# 12v-5v_conventer.net
KiCad netlist of a schematic drawn in Altium Designer
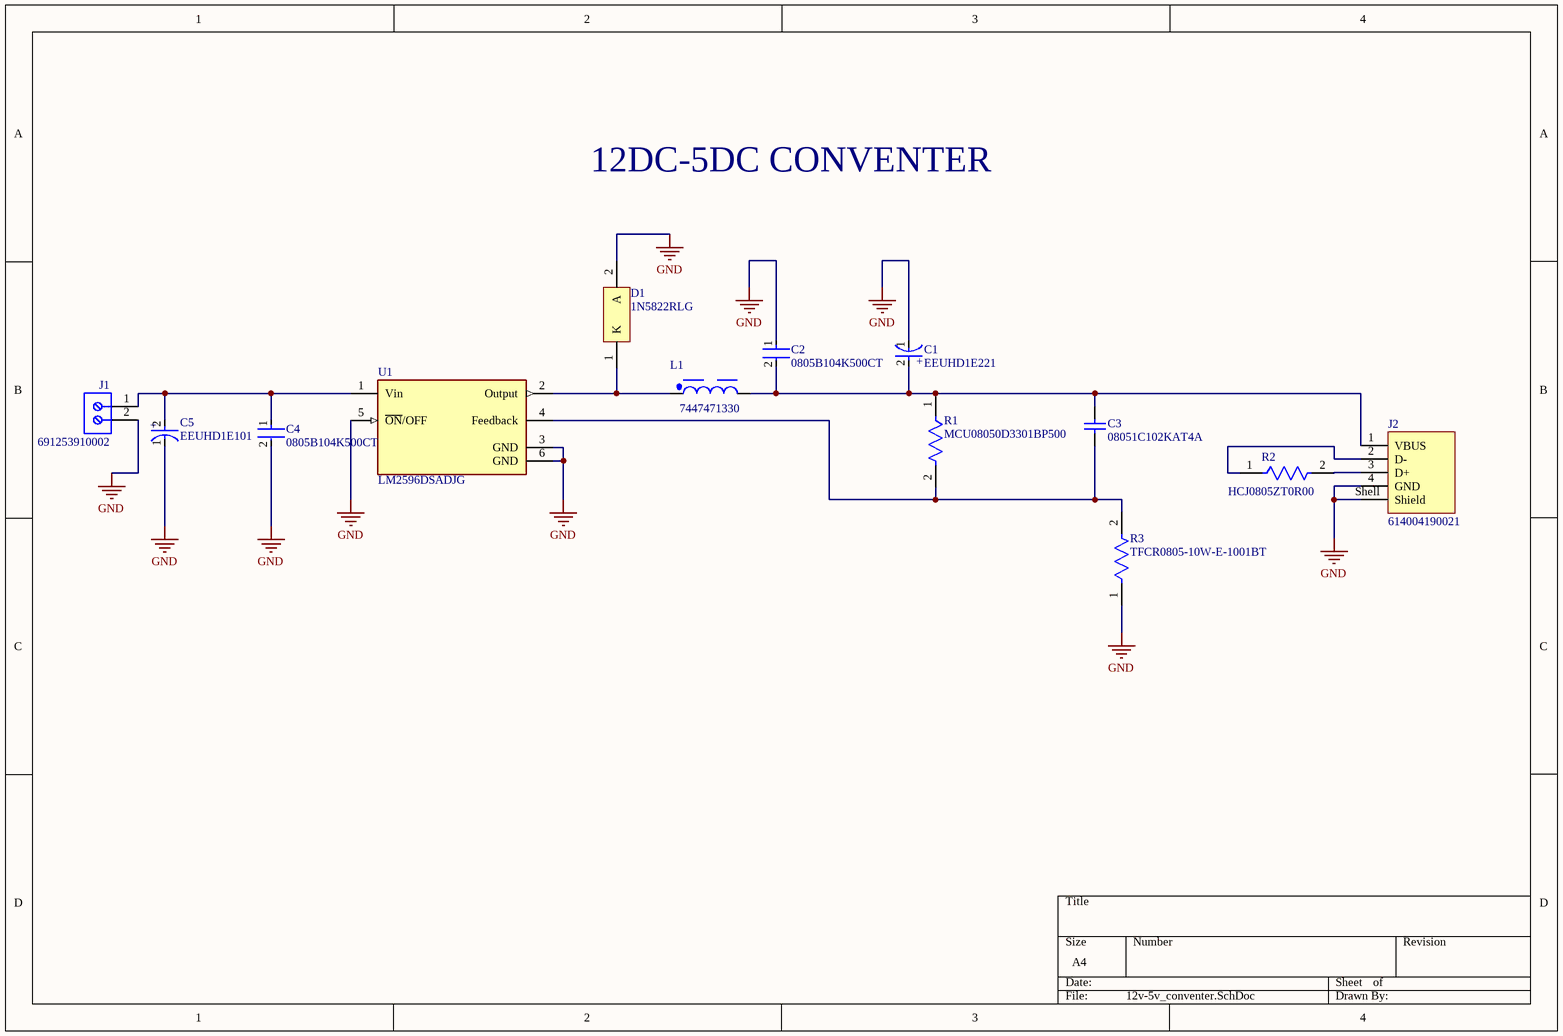
[diagram p0: 12v-5v_conventer.SchDoc]

(export (version "E")
  (design (tool "Eeschema 10.0.6"))
  (components
    (comp (ref "C1")
      (value "EEUHD1E221")
      (footprint "FP-RAD-TH-D_8_0_5-L_11_5-MFG")
      (description "Aluminum Electrolytic Capacitors (Radial Lead Type) AEC-Q200 Qualified 220uF ±20% 25V")
      (fields (field (name "VOLTAGE") "25V") (field (name "TOLERANCE") "20%"))
      (libsource (lib "Altium Content Vault") (part "a00bbbee19879c290e62620ae7e47b1"))
    )
    (comp (ref "C2")
      (value "0805B104K500CT")
      (footprint "FP-0805B-IPC_C")
      (description "CAP CER 0.1UF 50V X7R 0805")
      (fields (field (name "VOLTAGE") "50V") (field (name "TOLERANCE") "10%"))
      (libsource (lib "Altium Content Vault") (part "02cd4be3c70576c341d710602a673aa"))
    )
    (comp (ref "C3")
      (value "08051C102KAT4A")
      (footprint "CAPC2013X94X50LL20T25")
      (fields (field (name "MANUFACTURER") "AVX Interconnect / Elco"))
      (libsource (lib "Altium Content Vault") (part "CAP"))
    )
    (comp (ref "C4")
      (value "0805B104K500CT")
      (footprint "FP-0805B-IPC_C")
      (description "CAP CER 0.1UF 50V X7R 0805")
      (fields (field (name "VOLTAGE") "50V") (field (name "TOLERANCE") "10%"))
      (libsource (lib "Altium Content Vault") (part "02cd4be3c70576c341d710602a673aa"))
    )
    (comp (ref "C5")
      (value "EEUHD1E101")
      (footprint "FP-RAD-TH-D_6_3_0_5-L_11-MFG")
      (description "Aluminum Electrolytic Capacitors (Radial Lead Type) AEC-Q200 Qualified 100uF ±20% 25V")
      (fields (field (name "TOLERANCE") "20%") (field (name "VOLTAGE") "25V"))
      (libsource (lib "Altium Content Vault") (part "a00bbbee19879c290e62620ae7e47b1"))
    )
    (comp (ref "D1")
      (value "1N5822RLG")
      (footprint "ONSC-AXIAL_LEAD-2-267-05_V")
      (description "Rectifier, 2-Pin Axial_Lead, Pb-Free, Tape and Reel")
      (fields (field (name "MANUFACTURER") "On Semiconductor"))
      (libsource (lib "Altium Content Vault") (part "ONSC-D-K1A2-2_A"))
    )
    (comp (ref "J1")
      (value "691253910002")
      (footprint "691253910002")
      (description "Terminal Block, 7.5MM Pitch, Horizontal, Rising Cage Clamp, 12-30 AWG, 2 Pin")
      (libsource (lib "Altium Content Vault") (part "TBL - 1R - 02P - Screw"))
    )
    (comp (ref "J2")
      (value "614004190021")
      (footprint "614004190021")
      (libsource (lib "Altium Content Vault") (part "USB 2.0_Type A_Receptacle_1 Port"))
    )
    (comp (ref "L1")
      (value "7447471330")
      (footprint "WE-TIS_1111")
      (description "Inductor Power Shielded Wirewound 33uH 20% 1KHz Ferrite 3.6A 61mOhm DCR RDL Tray")
      (fields (field (name "TOLERANCE") "20%"))
      (libsource (lib "Altium Content Vault") (part "Inductor - 2"))
    )
    (comp (ref "R1")
      (value "MCU08050D3301BP500")
      (footprint "FP-MCU0805-IPC_A")
      (description "RES 1.05K OHM 0.5% 1/5W 0805")
      (fields (field (name "TOLERANCE") "0.1%"))
      (libsource (lib "Altium Content Vault") (part "1029c3af85768c4190bb7ad29bc67b5"))
    )
    (comp (ref "R2")
      (value "HCJ0805ZT0R00")
      (footprint "FP-HCJ0805-MFG")
      (description "RES 0 OHM JUMPER 1/2W 0805")
      (libsource (lib "Altium Content Vault") (part "1029c3af85768c4190bb7ad29bc67b5"))
    )
    (comp (ref "R3")
      (value "TFCR0805-10W-E-1001BT")
      (footprint "FP-TFCR0805-IPC_A")
      (description "RES Thin Film,  1kΩ, 0.1%, 0.1W, 25ppm/°C, 0805")
      (libsource (lib "Altium Content Vault") (part "1029c3af85768c4190bb7ad29bc67b5"))
    )
    (comp (ref "U1")
      (value "LM2596DSADJG")
      (footprint "FP-936A-02-MFG")
      (description "IC REG MULT CONFG ADJ 3A D2PAK-5")
      (fields
        (field (name "OCTOPART") "https://octopart.com/lm2596dsadjg-on+semiconductor-12437034")
        (field (name "MANUFACTURER") "ON Semiconductor")
      )
      (libsource (lib "Altium Content Vault") (part "6e009c68f80b765d55aa2e30e527964"))
    )
  )
  (nets
    (net (code "1") (name "GND") (class "Default")
      (node (ref "C1") (pin "1") (pinfunction "C_1") (pintype "passive"))
      (node (ref "C2") (pin "1") (pinfunction "1_1") (pintype "passive"))
      (node (ref "C4") (pin "2") (pinfunction "2_2") (pintype "passive"))
      (node (ref "C5") (pin "1") (pinfunction "C_1") (pintype "passive"))
      (node (ref "D1") (pin "2") (pinfunction "A_2") (pintype "passive"))
      (node (ref "J1") (pin "2") (pinfunction "2_2") (pintype "passive"))
      (node (ref "J2") (pin "4") (pinfunction "GND_4") (pintype "passive"))
      (node (ref "J2") (pin "Shell") (pinfunction "Shield_Shell") (pintype "passive"))
      (node (ref "R3") (pin "1") (pinfunction "1_1") (pintype "passive"))
      (node (ref "U1") (pin "3") (pinfunction "GND_3") (pintype "power_in"))
      (node (ref "U1") (pin "5") (pinfunction "~{ON}/OFF_5") (pintype "input"))
      (node (ref "U1") (pin "6") (pinfunction "GND_6") (pintype "power_in"))
    )
    (net (code "2") (name "Net-(C1-A)") (class "Default")
      (node (ref "C1") (pin "2") (pinfunction "A_2") (pintype "passive"))
      (node (ref "C2") (pin "2") (pinfunction "2_2") (pintype "passive"))
      (node (ref "C3") (pin "2") (pinfunction "2_2") (pintype "passive"))
      (node (ref "J2") (pin "1") (pinfunction "VBUS_1") (pintype "passive"))
      (node (ref "L1") (pin "2") (pinfunction "2_2") (pintype "passive"))
      (node (ref "R1") (pin "1") (pinfunction "1_1") (pintype "passive"))
    )
    (net (code "3") (name "Net-(C5-A)") (class "Default")
      (node (ref "C4") (pin "1") (pinfunction "1_1") (pintype "passive"))
      (node (ref "C5") (pin "2") (pinfunction "A_2") (pintype "passive"))
      (node (ref "J1") (pin "1") (pinfunction "1_1") (pintype "passive"))
      (node (ref "U1") (pin "1") (pinfunction "Vin_1") (pintype "power_in"))
    )
    (net (code "4") (name "Net-(D1-K)") (class "Default")
      (node (ref "D1") (pin "1") (pinfunction "K_1") (pintype "passive"))
      (node (ref "L1") (pin "1") (pinfunction "1_1") (pintype "passive"))
      (node (ref "U1") (pin "2") (pinfunction "Output_2") (pintype "output"))
    )
    (net (code "5") (name "Net-(J2-D+)") (class "Default")
      (node (ref "J2") (pin "3") (pinfunction "D+_3") (pintype "passive"))
      (node (ref "R2") (pin "2") (pinfunction "2_2") (pintype "passive"))
    )
    (net (code "6") (name "Net-(J2-D-)") (class "Default")
      (node (ref "J2") (pin "2") (pinfunction "D-_2") (pintype "passive"))
      (node (ref "R2") (pin "1") (pinfunction "1_1") (pintype "passive"))
    )
    (net (code "7") (name "Net-(U1-Feedback)") (class "Default")
      (node (ref "C3") (pin "1") (pinfunction "1_1") (pintype "passive"))
      (node (ref "R1") (pin "2") (pinfunction "2_2") (pintype "passive"))
      (node (ref "R3") (pin "2") (pinfunction "2_2") (pintype "passive"))
      (node (ref "U1") (pin "4") (pinfunction "Feedback_4") (pintype "passive"))
    )
  )
)
